# NRF.net
KiCad netlist of a schematic drawn in Altium Designer
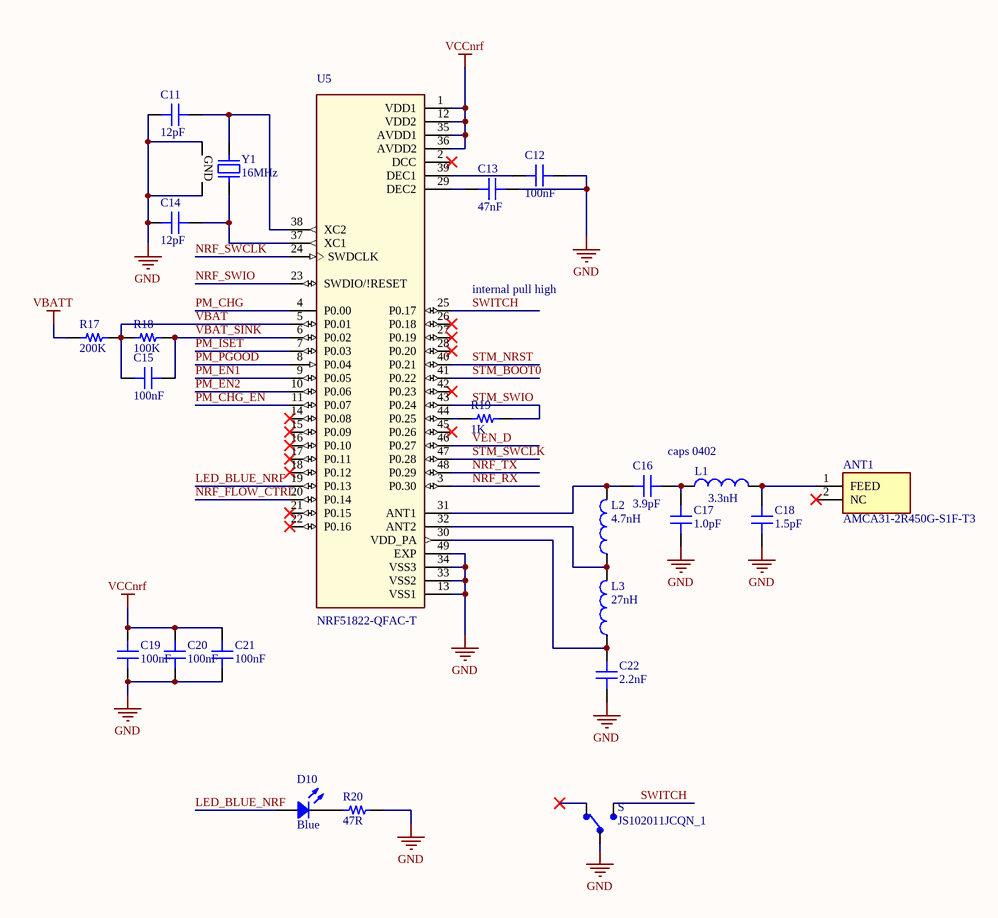
[diagram p0: NRF.SchDoc]

(export (version "E")
  (design (tool "Eeschema 10.0.6"))
  (components
    (comp (ref "ANT1")
      (value "AMCA31-2R450G-S1F-T3")
      (footprint "SamacSys:ANTC3216X140N")
      (description "Antenna")
      (fields (field (name "MOUSER PART NUMBER") "815-CA312R450GS1FT3"))
      (libsource (lib "altium-import") (part "root_0_AMCA31-2R450G-S1F-T3_"))
    )
    (comp (ref "C11")
      (value "12pF")
      (footprint "CAP 0402_1005")
      (description "CAP CER 12PF 50V C0G/NP0 0402")
      (fields (field (name "PART NUMBER") "04025A120GAT2A") (field (name "MANUFACTURER") "AVX Corporation"))
      (libsource (lib "Celestial Altium Library - altium_library") (part "Capacitor"))
    )
    (comp (ref "C12")
      (value "100nF")
      (footprint "CAP 0402_1005")
      (description "CAP CER 0.1UF 16V Y5V 0402")
      (fields (field (name "PART NUMBER") "C0402C104M4VACTU") (field (name "MANUFACTURER") "KEMET"))
      (libsource (lib "Celestial Altium Library - altium_library") (part "Capacitor"))
    )
    (comp (ref "C13")
      (value "47nF")
      (footprint "CAP 0402_1005")
      (description "CAP CER 0.1UF 16V Y5V 0402")
      (fields (field (name "PART NUMBER") "C0402C104M4VACTU") (field (name "MANUFACTURER") "KEMET"))
      (libsource (lib "Celestial Altium Library - altium_library") (part "Capacitor"))
    )
    (comp (ref "C14")
      (value "12pF")
      (footprint "CAP 0402_1005")
      (description "CAP CER 12PF 50V C0G/NP0 0402")
      (fields (field (name "PART NUMBER") "04025A120GAT2A") (field (name "MANUFACTURER") "AVX Corporation"))
      (libsource (lib "Celestial Altium Library - altium_library") (part "Capacitor"))
    )
    (comp (ref "C15")
      (value "100nF")
      (footprint "CAP 0402_1005")
      (description "CAP CER 0.1UF 16V Y5V 0402")
      (fields (field (name "PART NUMBER") "C0402C104M4VACTU") (field (name "MANUFACTURER") "KEMET"))
      (libsource (lib "Celestial Altium Library - altium_library") (part "Capacitor"))
    )
    (comp (ref "C16")
      (value "3.9pF")
      (footprint "CAP 0402_1005")
      (description "CAP CER 0.1UF 16V Y5V 0402")
      (fields (field (name "PART NUMBER") "C0402C104M4VACTU") (field (name "MANUFACTURER") "KEMET"))
      (libsource (lib "Celestial Altium Library - altium_library") (part "Capacitor"))
    )
    (comp (ref "C17")
      (value "1.0pF")
      (footprint "CAP 0402_1005")
      (description "CAP CER 0.1UF 16V Y5V 0402")
      (fields (field (name "PART NUMBER") "C0402C104M4VACTU") (field (name "MANUFACTURER") "KEMET"))
      (libsource (lib "Celestial Altium Library - altium_library") (part "Capacitor"))
    )
    (comp (ref "C18")
      (value "1.5pF")
      (footprint "CAP 0402_1005")
      (description "CAP CER 0.1UF 16V Y5V 0402")
      (fields (field (name "PART NUMBER") "C0402C104M4VACTU") (field (name "MANUFACTURER") "KEMET"))
      (libsource (lib "Celestial Altium Library - altium_library") (part "Capacitor"))
    )
    (comp (ref "C19")
      (value "100nF")
      (footprint "CAP 0402_1005")
      (description "CAP CER 0.1UF 16V Y5V 0402")
      (fields (field (name "PART NUMBER") "C0402C104M4VACTU") (field (name "MANUFACTURER") "KEMET"))
      (libsource (lib "Celestial Altium Library - altium_library") (part "Capacitor"))
    )
    (comp (ref "C20")
      (value "100nF")
      (footprint "CAP 0402_1005")
      (description "CAP CER 0.1UF 16V Y5V 0402")
      (fields (field (name "PART NUMBER") "C0402C104M4VACTU") (field (name "MANUFACTURER") "KEMET"))
      (libsource (lib "Celestial Altium Library - altium_library") (part "Capacitor"))
    )
    (comp (ref "C21")
      (value "100nF")
      (footprint "CAP 0402_1005")
      (description "CAP CER 0.1UF 16V Y5V 0402")
      (fields (field (name "PART NUMBER") "C0402C104M4VACTU") (field (name "MANUFACTURER") "KEMET"))
      (libsource (lib "Celestial Altium Library - altium_library") (part "Capacitor"))
    )
    (comp (ref "C22")
      (value "2.2nF")
      (footprint "CAP 0402_1005")
      (description "CAP CER 0.1UF 16V Y5V 0402")
      (fields (field (name "PART NUMBER") "C0402C104M4VACTU") (field (name "MANUFACTURER") "KEMET"))
      (libsource (lib "Celestial Altium Library - altium_library") (part "Capacitor"))
    )
    (comp (ref "D10")
      (value "Blue")
      (footprint "LED 0603_1608 BLUE")
      (description "LED BLUE CLEAR 2SMD")
      (fields (field (name "PART NUMBER") "XZFBB53W-1") (field (name "MANUFACTURER") "SunLED"))
      (libsource (lib "Celestial Altium Library - altium_library") (part "LED"))
    )
    (comp (ref "L1")
      (value "3.3nH")
      (footprint "0402-A")
      (description "Inductor")
      (fields (field (name "PUBLISHER") "Altium Limited"))
      (libsource (lib "Miscellaneous Devices") (part "Inductor"))
    )
    (comp (ref "L2")
      (value "4.7nH")
      (footprint "0402-A")
      (description "Inductor")
      (fields (field (name "PUBLISHER") "Altium Limited"))
      (libsource (lib "Miscellaneous Devices") (part "Inductor"))
    )
    (comp (ref "L3")
      (value "27nH")
      (footprint "0402-A")
      (description "Inductor")
      (fields (field (name "PUBLISHER") "Altium Limited"))
      (libsource (lib "Miscellaneous Devices") (part "Inductor"))
    )
    (comp (ref "R17")
      (value "200K")
      (footprint "RES 0402_1005")
      (description "RES SMD 4.7K OHM 1% 1/16W 0402")
      (fields (field (name "PART NUMBER") "RT0402FRE074K7L") (field (name "MANUFACTURER") "Yageo"))
      (libsource (lib "Celestial Altium Library - altium_library") (part "Resistor"))
    )
    (comp (ref "R18")
      (value "100K")
      (footprint "RES 0402_1005")
      (description "RES SMD 4.7K OHM 1% 1/16W 0402")
      (fields (field (name "PART NUMBER") "RT0402FRE074K7L") (field (name "MANUFACTURER") "Yageo"))
      (libsource (lib "Celestial Altium Library - altium_library") (part "Resistor"))
    )
    (comp (ref "R19")
      (value "1K")
      (footprint "RES 0402_1005")
      (description "RES SMD 4.7K OHM 1% 1/16W 0402")
      (fields (field (name "PART NUMBER") "RT0402FRE074K7L") (field (name "MANUFACTURER") "Yageo"))
      (libsource (lib "Celestial Altium Library - altium_library") (part "Resistor"))
    )
    (comp (ref "R20")
      (value "47R")
      (footprint "RES 0402_1005")
      (description "RES SMD 4.7K OHM 1% 1/16W 0402")
      (fields (field (name "PART NUMBER") "RT0402FRE074K7L") (field (name "MANUFACTURER") "Yageo"))
      (libsource (lib "Celestial Altium Library - altium_library") (part "Resistor"))
    )
    (comp (ref "S")
      (value "JS102011JCQN_1")
      (footprint "SW_JS102011JCQN")
      (description "Slide Switch SPDT Surface Mount")
      (fields (field (name "MF") "C&K") (field (name "MP") "JS102011JCQN"))
      (libsource (lib "Schlib1") (part "JS102011JCQN_1"))
    )
    (comp (ref "U5")
      (value "NRF51822-QFAC-T")
      (footprint "*QFN40P600X600X90-49N")
      (libsource (lib "Schlib1") (part "NRF51822-QFAC-T"))
    )
    (comp (ref "Y1")
      (value "16MHz")
      (footprint "ABRACON ABM8G")
      (description "CRYSTAL 16.0000MHZ 10PF SMD")
      (fields
        (field (name "PART NUMBER") "ABM8G-16.000MHZ-B4Y-T")
        (field (name "MANUFACTURER") "Abracon LLC")
      )
      (libsource (lib "Celestial Altium Library - altium_library") (part "Abracon Crystal ABM8G"))
    )
  )
  (nets
    (net (code "1") (name "/LED_BLUE_NRF") (class "Default")
      (node (ref "D10") (pin "1") (pinfunction "1_1") (pintype "passive"))
      (node (ref "U5") (pin "19") (pinfunction "P0.13_19") (pintype "bidirectional"))
    )
    (net (code "2") (name "/NRF_FLOW_CTRL") (class "Default")
      (node (ref "U5") (pin "20") (pinfunction "P0.14_20") (pintype "bidirectional"))
    )
    (net (code "3") (name "/NRF_RX") (class "Default")
      (node (ref "U5") (pin "3") (pinfunction "P0.30_3") (pintype "bidirectional"))
    )
    (net (code "4") (name "/NRF_SWCLK") (class "Default")
      (node (ref "U5") (pin "24") (pinfunction "SWDCLK_24") (pintype "input"))
    )
    (net (code "5") (name "/NRF_SWIO") (class "Default")
      (node (ref "U5") (pin "23") (pinfunction "SWDIO/!RESET_23") (pintype "bidirectional"))
    )
    (net (code "6") (name "/NRF_TX") (class "Default")
      (node (ref "U5") (pin "48") (pinfunction "P0.29_48") (pintype "bidirectional"))
    )
    (net (code "7") (name "/PM_CHG") (class "Default")
      (node (ref "U5") (pin "4") (pinfunction "P0.00_4") (pintype "passive"))
    )
    (net (code "8") (name "/PM_CHG_EN") (class "Default")
      (node (ref "U5") (pin "11") (pinfunction "P0.07_11") (pintype "bidirectional"))
    )
    (net (code "9") (name "/PM_EN1") (class "Default")
      (node (ref "U5") (pin "9") (pinfunction "P0.05_9") (pintype "bidirectional"))
    )
    (net (code "10") (name "/PM_EN2") (class "Default")
      (node (ref "U5") (pin "10") (pinfunction "P0.06_10") (pintype "bidirectional"))
    )
    (net (code "11") (name "/PM_ISET") (class "Default")
      (node (ref "U5") (pin "7") (pinfunction "P0.03_7") (pintype "bidirectional"))
    )
    (net (code "12") (name "/PM_PGOOD") (class "Default")
      (node (ref "U5") (pin "8") (pinfunction "P0.04_8") (pintype "input"))
    )
    (net (code "13") (name "/STM_BOOT0") (class "Default")
      (node (ref "U5") (pin "41") (pinfunction "P0.22_41") (pintype "bidirectional"))
    )
    (net (code "14") (name "/STM_NRST") (class "Default")
      (node (ref "U5") (pin "40") (pinfunction "P0.21_40") (pintype "bidirectional"))
    )
    (net (code "15") (name "/STM_SWCLK") (class "Default")
      (node (ref "U5") (pin "47") (pinfunction "P0.28_47") (pintype "bidirectional"))
    )
    (net (code "16") (name "/STM_SWIO") (class "Default")
      (node (ref "R19") (pin "2") (pinfunction "2_2") (pintype "passive"))
      (node (ref "U5") (pin "43") (pinfunction "P0.24_43") (pintype "bidirectional"))
    )
    (net (code "17") (name "/SWITCH") (class "Default")
      (node (ref "S") (pin "3") (pinfunction "3_3") (pintype "passive"))
      (node (ref "U5") (pin "25") (pinfunction "P0.17_25") (pintype "bidirectional"))
    )
    (net (code "18") (name "/VBAT") (class "Default")
      (node (ref "C15") (pin "2") (pinfunction "2_2") (pintype "passive"))
      (node (ref "R17") (pin "2") (pinfunction "2_2") (pintype "passive"))
      (node (ref "R18") (pin "1") (pinfunction "1_1") (pintype "passive"))
      (node (ref "U5") (pin "5") (pinfunction "P0.01_5") (pintype "bidirectional"))
    )
    (net (code "19") (name "/VBAT_SINK") (class "Default")
      (node (ref "C15") (pin "1") (pinfunction "1_1") (pintype "passive"))
      (node (ref "R18") (pin "2") (pinfunction "2_2") (pintype "passive"))
      (node (ref "U5") (pin "6") (pinfunction "P0.02_6") (pintype "bidirectional"))
    )
    (net (code "20") (name "/VEN_D") (class "Default")
      (node (ref "U5") (pin "46") (pinfunction "P0.27_46") (pintype "bidirectional"))
    )
    (net (code "21") (name "GND") (class "Default")
      (node (ref "C11") (pin "1") (pinfunction "1_1") (pintype "passive"))
      (node (ref "C12") (pin "1") (pinfunction "1_1") (pintype "passive"))
      (node (ref "C13") (pin "1") (pinfunction "1_1") (pintype "passive"))
      (node (ref "C14") (pin "1") (pinfunction "1_1") (pintype "passive"))
      (node (ref "C17") (pin "1") (pinfunction "1_1") (pintype "passive"))
      (node (ref "C18") (pin "1") (pinfunction "1_1") (pintype "passive"))
      (node (ref "C19") (pin "1") (pinfunction "1_1") (pintype "passive"))
      (node (ref "C20") (pin "1") (pinfunction "1_1") (pintype "passive"))
      (node (ref "C21") (pin "1") (pinfunction "1_1") (pintype "passive"))
      (node (ref "C22") (pin "1") (pinfunction "1_1") (pintype "passive"))
      (node (ref "R20") (pin "2") (pinfunction "2_2") (pintype "passive"))
      (node (ref "S") (pin "2") (pinfunction "2_2") (pintype "passive"))
      (node (ref "U5") (pin "13") (pinfunction "VSS1_13") (pintype "power_in"))
      (node (ref "U5") (pin "33") (pinfunction "VSS2_33") (pintype "power_in"))
      (node (ref "U5") (pin "34") (pinfunction "VSS3_34") (pintype "power_in"))
      (node (ref "U5") (pin "49") (pinfunction "EXP_49") (pintype "power_in"))
      (node (ref "Y1") (pin "2") (pinfunction "GND_2") (pintype "passive"))
      (node (ref "Y1") (pin "4") (pinfunction "GND_4") (pintype "passive"))
    )
    (net (code "22") (name "Net-(ANT1-FEED)") (class "Default")
      (node (ref "ANT1") (pin "1") (pinfunction "FEED_1") (pintype "passive"))
      (node (ref "C18") (pin "2") (pinfunction "2_2") (pintype "passive"))
      (node (ref "L1") (pin "2") (pinfunction "2_2") (pintype "passive"))
    )
    (net (code "23") (name "Net-(C16-Pad2)") (class "Default")
      (node (ref "C16") (pin "2") (pinfunction "2_2") (pintype "passive"))
      (node (ref "C17") (pin "2") (pinfunction "2_2") (pintype "passive"))
      (node (ref "L1") (pin "1") (pinfunction "1_1") (pintype "passive"))
    )
    (net (code "24") (name "Net-(D10-Pad2)") (class "Default")
      (node (ref "D10") (pin "2") (pinfunction "2_2") (pintype "passive"))
      (node (ref "R20") (pin "1") (pinfunction "1_1") (pintype "passive"))
    )
    (net (code "25") (name "Net-(U5-ANT1)") (class "Default")
      (node (ref "C16") (pin "1") (pinfunction "1_1") (pintype "passive"))
      (node (ref "L2") (pin "2") (pinfunction "2_2") (pintype "passive"))
      (node (ref "U5") (pin "31") (pinfunction "ANT1_31") (pintype "passive"))
    )
    (net (code "26") (name "Net-(U5-ANT2)") (class "Default")
      (node (ref "L2") (pin "1") (pinfunction "1_1") (pintype "passive"))
      (node (ref "L3") (pin "2") (pinfunction "2_2") (pintype "passive"))
      (node (ref "U5") (pin "32") (pinfunction "ANT2_32") (pintype "passive"))
    )
    (net (code "27") (name "Net-(U5-DEC1)") (class "Default")
      (node (ref "C12") (pin "2") (pinfunction "2_2") (pintype "passive"))
      (node (ref "U5") (pin "39") (pinfunction "DEC1_39") (pintype "power_in"))
    )
    (net (code "28") (name "Net-(U5-DEC2)") (class "Default")
      (node (ref "C13") (pin "2") (pinfunction "2_2") (pintype "passive"))
      (node (ref "U5") (pin "29") (pinfunction "DEC2_29") (pintype "power_in"))
    )
    (net (code "29") (name "Net-(U5-P0.25)") (class "Default")
      (node (ref "R19") (pin "1") (pinfunction "1_1") (pintype "passive"))
      (node (ref "U5") (pin "44") (pinfunction "P0.25_44") (pintype "bidirectional"))
    )
    (net (code "30") (name "Net-(U5-VDD_PA)") (class "Default")
      (node (ref "C22") (pin "2") (pinfunction "2_2") (pintype "passive"))
      (node (ref "L3") (pin "1") (pinfunction "1_1") (pintype "passive"))
      (node (ref "U5") (pin "30") (pinfunction "VDD_PA_30") (pintype "output"))
    )
    (net (code "31") (name "Net-(U5-XC1)") (class "Default")
      (node (ref "C14") (pin "2") (pinfunction "2_2") (pintype "passive"))
      (node (ref "U5") (pin "37") (pinfunction "XC1_37") (pintype "output"))
      (node (ref "Y1") (pin "3") (pinfunction "3_3") (pintype "passive"))
    )
    (net (code "32") (name "Net-(U5-XC2)") (class "Default")
      (node (ref "C11") (pin "2") (pinfunction "2_2") (pintype "passive"))
      (node (ref "U5") (pin "38") (pinfunction "XC2_38") (pintype "output"))
      (node (ref "Y1") (pin "1") (pinfunction "1_1") (pintype "passive"))
    )
    (net (code "33") (name "VBATT") (class "Default")
      (node (ref "R17") (pin "1") (pinfunction "1_1") (pintype "passive"))
    )
    (net (code "34") (name "VCCnrf") (class "Default")
      (node (ref "C19") (pin "2") (pinfunction "2_2") (pintype "passive"))
      (node (ref "C20") (pin "2") (pinfunction "2_2") (pintype "passive"))
      (node (ref "C21") (pin "2") (pinfunction "2_2") (pintype "passive"))
      (node (ref "U5") (pin "1") (pinfunction "VDD1_1") (pintype "power_in"))
      (node (ref "U5") (pin "12") (pinfunction "VDD2_12") (pintype "power_in"))
      (node (ref "U5") (pin "35") (pinfunction "AVDD1_35") (pintype "power_in"))
      (node (ref "U5") (pin "36") (pinfunction "AVDD2_36") (pintype "power_in"))
    )
    (net (code "35") (name "unconnected-(ANT1-NC-Pad2)") (class "Default")
      (node (ref "ANT1") (pin "2") (pinfunction "NC_2") (pintype "passive+no_connect"))
    )
    (net (code "36") (name "unconnected-(S-Pad1)") (class "Default")
      (node (ref "S") (pin "1") (pinfunction "1_1") (pintype "passive+no_connect"))
    )
    (net (code "37") (name "unconnected-(U5-DCC-Pad2)") (class "Default")
      (node (ref "U5") (pin "2") (pinfunction "DCC_2") (pintype "power_in+no_connect"))
    )
    (net (code "38") (name "unconnected-(U5-P0.08-Pad14)") (class "Default")
      (node (ref "U5") (pin "14") (pinfunction "P0.08_14") (pintype "bidirectional+no_connect"))
    )
    (net (code "39") (name "unconnected-(U5-P0.09-Pad15)") (class "Default")
      (node (ref "U5") (pin "15") (pinfunction "P0.09_15") (pintype "bidirectional+no_connect"))
    )
    (net (code "40") (name "unconnected-(U5-P0.10-Pad16)") (class "Default")
      (node (ref "U5") (pin "16") (pinfunction "P0.10_16") (pintype "bidirectional+no_connect"))
    )
    (net (code "41") (name "unconnected-(U5-P0.11-Pad17)") (class "Default")
      (node (ref "U5") (pin "17") (pinfunction "P0.11_17") (pintype "bidirectional+no_connect"))
    )
    (net (code "42") (name "unconnected-(U5-P0.12-Pad18)") (class "Default")
      (node (ref "U5") (pin "18") (pinfunction "P0.12_18") (pintype "bidirectional+no_connect"))
    )
    (net (code "43") (name "unconnected-(U5-P0.15-Pad21)") (class "Default")
      (node (ref "U5") (pin "21") (pinfunction "P0.15_21") (pintype "bidirectional+no_connect"))
    )
    (net (code "44") (name "unconnected-(U5-P0.16-Pad22)") (class "Default")
      (node (ref "U5") (pin "22") (pinfunction "P0.16_22") (pintype "bidirectional+no_connect"))
    )
    (net (code "45") (name "unconnected-(U5-P0.18-Pad26)") (class "Default")
      (node (ref "U5") (pin "26") (pinfunction "P0.18_26") (pintype "bidirectional+no_connect"))
    )
    (net (code "46") (name "unconnected-(U5-P0.19-Pad27)") (class "Default")
      (node (ref "U5") (pin "27") (pinfunction "P0.19_27") (pintype "bidirectional+no_connect"))
    )
    (net (code "47") (name "unconnected-(U5-P0.20-Pad28)") (class "Default")
      (node (ref "U5") (pin "28") (pinfunction "P0.20_28") (pintype "bidirectional+no_connect"))
    )
    (net (code "48") (name "unconnected-(U5-P0.23-Pad42)") (class "Default")
      (node (ref "U5") (pin "42") (pinfunction "P0.23_42") (pintype "bidirectional+no_connect"))
    )
    (net (code "49") (name "unconnected-(U5-P0.26-Pad45)") (class "Default")
      (node (ref "U5") (pin "45") (pinfunction "P0.26_45") (pintype "bidirectional+no_connect"))
    )
  )
)
